# linear_buffered_sense.net
KiCad netlist of a schematic drawn in Altium Designer
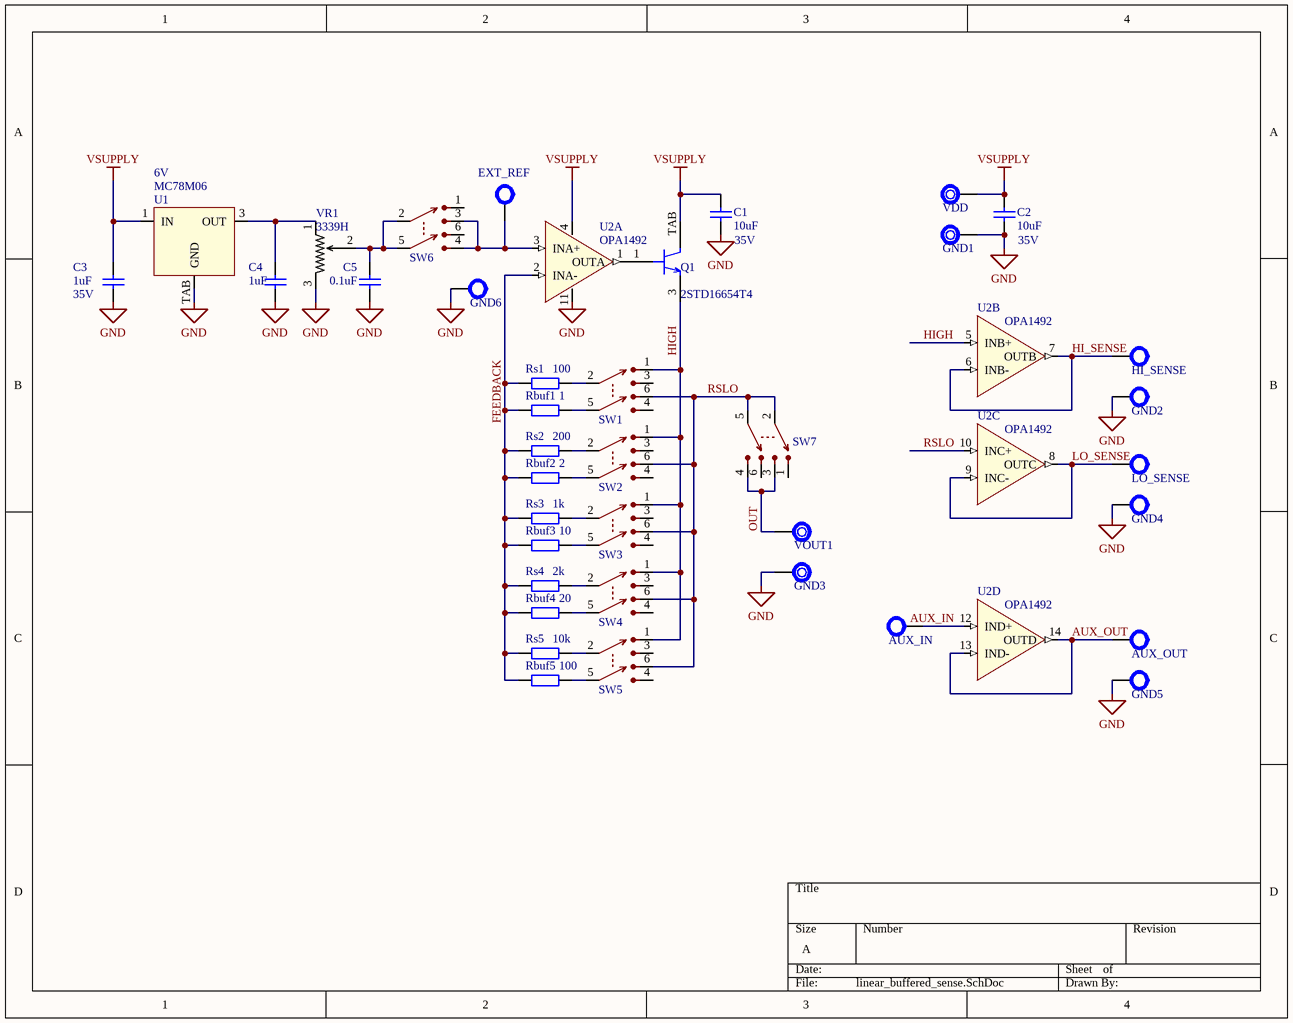
[diagram p0: linear_buffered_sense.SchDoc]

(export (version "E")
  (design (tool "Eeschema 10.0.6"))
  (components
    (comp (ref "AUX_IN")
      (value "Test Point")
      (footprint "Test Point - Large")
      (description "Test Point, large or small foot prints")
      (fields
        (field (name "MANUFACTURER PART NUMBER") "Example: 5000, 5013")
        (field (name "MANUFACTURER") "Keystone Electronics")
      )
      (libsource (lib "wisp") (part "Test Point"))
    )
    (comp (ref "AUX_OUT")
      (value "Test Point")
      (footprint "Test Point - Large")
      (description "Test Point, large or small foot prints")
      (fields
        (field (name "MANUFACTURER PART NUMBER") "Example: 5000, 5013")
        (field (name "MANUFACTURER") "Keystone Electronics")
      )
      (libsource (lib "wisp") (part "Test Point"))
    )
    (comp (ref "C1")
      (value "10uF")
      (footprint "1210-W")
      (description "Ceramic Capacitor (Surface Mount)")
      (fields
        (field (name "MANUFACTURER") "Generic Ceramic Chip Cap (TBD)")
        (field (name "RATING") "35V")
        (field (name "Comment") "Cap")
      )
      (libsource (lib "wisp") (part "Cap"))
    )
    (comp (ref "C2")
      (value "10uF")
      (footprint "1210-W")
      (description "Ceramic Capacitor (Surface Mount)")
      (fields
        (field (name "MANUFACTURER") "Generic Ceramic Chip Cap (TBD)")
        (field (name "RATING") "35V")
        (field (name "Comment") "Cap")
      )
      (libsource (lib "wisp") (part "Cap"))
    )
    (comp (ref "C3")
      (value "1uF")
      (footprint "0805")
      (description "Ceramic Capacitor (Surface Mount)")
      (fields
        (field (name "MANUFACTURER") "Generic Ceramic Chip Cap (TBD)")
        (field (name "RATING") "35V")
        (field (name "Comment") "Cap")
      )
      (libsource (lib "wisp") (part "Cap"))
    )
    (comp (ref "C4")
      (value "1uF")
      (footprint "0805")
      (description "Ceramic Capacitor (Surface Mount)")
      (fields (field (name "MANUFACTURER") "Generic Ceramic Chip Cap (TBD)") (field (name "Comment") "Cap"))
      (libsource (lib "wisp") (part "Cap"))
    )
    (comp (ref "C5")
      (value "0.1uF")
      (footprint "0805")
      (description "Ceramic Capacitor (Surface Mount)")
      (fields (field (name "MANUFACTURER") "Generic Ceramic Chip Cap (TBD)") (field (name "Comment") "Cap"))
      (libsource (lib "wisp") (part "Cap"))
    )
    (comp (ref "EXT_REF")
      (value "Test Point")
      (footprint "Test Point - Large")
      (description "Test Point, large or small foot prints")
      (fields
        (field (name "MANUFACTURER PART NUMBER") "Example: 5000, 5013")
        (field (name "MANUFACTURER") "Keystone Electronics")
      )
      (libsource (lib "wisp") (part "Test Point"))
    )
    (comp (ref "GND1")
      (value "BANANA")
      (footprint "BANANA")
      (description "Banana plug")
      (fields
        (field (name "MANUFACTURER PART NUMBER") "Example: 5000, 5013")
        (field (name "MANUFACTURER") "Keystone Electronics")
      )
      (libsource (lib "usmu") (part "BANANA"))
    )
    (comp (ref "GND2")
      (value "Test Point")
      (footprint "Test Point - Large")
      (description "Test Point, large or small foot prints")
      (fields
        (field (name "MANUFACTURER PART NUMBER") "Example: 5000, 5013")
        (field (name "MANUFACTURER") "Keystone Electronics")
      )
      (libsource (lib "wisp") (part "Test Point"))
    )
    (comp (ref "GND3")
      (value "BANANA")
      (footprint "BANANA")
      (description "Banana plug")
      (fields
        (field (name "MANUFACTURER PART NUMBER") "Example: 5000, 5013")
        (field (name "MANUFACTURER") "Keystone Electronics")
      )
      (libsource (lib "usmu") (part "BANANA"))
    )
    (comp (ref "GND4")
      (value "Test Point")
      (footprint "Test Point - Large")
      (description "Test Point, large or small foot prints")
      (fields
        (field (name "MANUFACTURER PART NUMBER") "Example: 5000, 5013")
        (field (name "MANUFACTURER") "Keystone Electronics")
      )
      (libsource (lib "wisp") (part "Test Point"))
    )
    (comp (ref "GND5")
      (value "Test Point")
      (footprint "Test Point - Large")
      (description "Test Point, large or small foot prints")
      (fields
        (field (name "MANUFACTURER PART NUMBER") "Example: 5000, 5013")
        (field (name "MANUFACTURER") "Keystone Electronics")
      )
      (libsource (lib "wisp") (part "Test Point"))
    )
    (comp (ref "GND6")
      (value "Test Point")
      (footprint "Test Point - Large")
      (description "Test Point, large or small foot prints")
      (fields
        (field (name "MANUFACTURER PART NUMBER") "Example: 5000, 5013")
        (field (name "MANUFACTURER") "Keystone Electronics")
      )
      (libsource (lib "wisp") (part "Test Point"))
    )
    (comp (ref "HI_SENSE")
      (value "Test Point")
      (footprint "Test Point - Large")
      (description "Test Point, large or small foot prints")
      (fields
        (field (name "MANUFACTURER PART NUMBER") "Example: 5000, 5013")
        (field (name "MANUFACTURER") "Keystone Electronics")
      )
      (libsource (lib "wisp") (part "Test Point"))
    )
    (comp (ref "LO_SENSE")
      (value "Test Point")
      (footprint "Test Point - Large")
      (description "Test Point, large or small foot prints")
      (fields
        (field (name "MANUFACTURER PART NUMBER") "Example: 5000, 5013")
        (field (name "MANUFACTURER") "Keystone Electronics")
      )
      (libsource (lib "wisp") (part "Test Point"))
    )
    (comp (ref "Q1")
      (value "2STD16654T4")
      (footprint "TO-252")
      (description "STMicroelectronics NPN BJT High Power")
      (fields
        (field (name "DIGI-KEY PART NUMBER") "568-6140-1-ND")
        (field (name "MANUFACTURER PART NUMBER") "BF1101WR,115")
      )
      (libsource (lib "usmu") (part "2STD16654T4"))
    )
    (comp (ref "Rbuf1")
      (value "1")
      (footprint "AXIAL-0.4")
      (description "Resistor")
      (fields (field (name "Comment") "Res2") (field (name "PUBLISHER") "Altium Limited"))
      (libsource (lib "altium-import") (part "root_2__Miscellaneous Devices.IntLib"))
    )
    (comp (ref "Rbuf2")
      (value "2")
      (footprint "AXIAL-0.4")
      (description "Resistor")
      (fields (field (name "Comment") "Res2") (field (name "PUBLISHER") "Altium Limited"))
      (libsource (lib "altium-import") (part "root_2__Miscellaneous Devices.IntLib"))
    )
    (comp (ref "Rbuf3")
      (value "10")
      (footprint "AXIAL-0.4")
      (description "Resistor")
      (fields (field (name "Comment") "Res2") (field (name "PUBLISHER") "Altium Limited"))
      (libsource (lib "altium-import") (part "root_2__Miscellaneous Devices.IntLib"))
    )
    (comp (ref "Rbuf4")
      (value "20")
      (footprint "AXIAL-0.4")
      (description "Resistor")
      (fields (field (name "Comment") "Res2") (field (name "PUBLISHER") "Altium Limited"))
      (libsource (lib "altium-import") (part "root_2__Miscellaneous Devices.IntLib"))
    )
    (comp (ref "Rbuf5")
      (value "100")
      (footprint "AXIAL-0.4")
      (description "Resistor")
      (fields (field (name "Comment") "Res2") (field (name "PUBLISHER") "Altium Limited"))
      (libsource (lib "altium-import") (part "root_2__Miscellaneous Devices.IntLib"))
    )
    (comp (ref "Rs1")
      (value "100")
      (footprint "AXIAL-0.4")
      (description "Resistor")
      (fields (field (name "Comment") "Res2") (field (name "PUBLISHER") "Altium Limited"))
      (libsource (lib "altium-import") (part "root_2__Miscellaneous Devices.IntLib"))
    )
    (comp (ref "Rs2")
      (value "200")
      (footprint "AXIAL-0.4")
      (description "Resistor")
      (fields (field (name "Comment") "Res2") (field (name "PUBLISHER") "Altium Limited"))
      (libsource (lib "altium-import") (part "root_2__Miscellaneous Devices.IntLib"))
    )
    (comp (ref "Rs3")
      (value "1k")
      (footprint "AXIAL-0.4")
      (description "Resistor")
      (fields (field (name "Comment") "Res2") (field (name "PUBLISHER") "Altium Limited"))
      (libsource (lib "altium-import") (part "root_2__Miscellaneous Devices.IntLib"))
    )
    (comp (ref "Rs4")
      (value "2k")
      (footprint "AXIAL-0.4")
      (description "Resistor")
      (fields (field (name "Comment") "Res2") (field (name "PUBLISHER") "Altium Limited"))
      (libsource (lib "altium-import") (part "root_2__Miscellaneous Devices.IntLib"))
    )
    (comp (ref "Rs5")
      (value "10k")
      (footprint "AXIAL-0.4")
      (description "Resistor")
      (fields (field (name "Comment") "Res2") (field (name "PUBLISHER") "Altium Limited"))
      (libsource (lib "altium-import") (part "root_2__Miscellaneous Devices.IntLib"))
    )
    (comp (ref "SW1")
      (value "JS202011CQN")
      (footprint "JS202011CQN_LABEL")
      (description "6-pin DPDT (tied) Slide Switch")
      (libsource (lib "usmu") (part "JS202011CQN_LABEL"))
    )
    (comp (ref "SW2")
      (value "JS202011CQN")
      (footprint "JS202011CQN_LABEL")
      (description "6-pin DPDT (tied) Slide Switch")
      (libsource (lib "usmu") (part "JS202011CQN_LABEL"))
    )
    (comp (ref "SW3")
      (value "JS202011CQN")
      (footprint "JS202011CQN_LABEL")
      (description "6-pin DPDT (tied) Slide Switch")
      (libsource (lib "usmu") (part "JS202011CQN_LABEL"))
    )
    (comp (ref "SW4")
      (value "JS202011CQN")
      (footprint "JS202011CQN_LABEL")
      (description "6-pin DPDT (tied) Slide Switch")
      (libsource (lib "usmu") (part "JS202011CQN_LABEL"))
    )
    (comp (ref "SW5")
      (value "JS202011CQN")
      (footprint "JS202011CQN_LABEL")
      (description "6-pin DPDT (tied) Slide Switch")
      (libsource (lib "usmu") (part "JS202011CQN_LABEL"))
    )
    (comp (ref "SW6")
      (value "JS202011CQN")
      (footprint "JS202011CQN")
      (description "6-pin DPDT (tied) Slide Switch")
      (libsource (lib "usmu") (part "JS202011CQN"))
    )
    (comp (ref "SW7")
      (value "JS202011CQN")
      (footprint "JS202011CQN")
      (description "6-pin DPDT (tied) Slide Switch")
      (libsource (lib "usmu") (part "JS202011CQN"))
    )
    (comp (ref "U1")
      (value "MC78M06")
      (footprint "TO-252")
      (description "500mA Positive Voltage Regulator")
      (fields (field (name "ALTIUM_VALUE") "6V"))
      (libsource (lib "usmu") (part "MC78M00"))
    )
    (comp (ref "U2")
      (value "OPA1492")
      (footprint "14-SOIC-TI")
      (description "OPAx192 Op-Amp Texas Instruments")
      (libsource (lib "usmu") (part "OPA1492"))
    )
    (comp (ref "VDD")
      (value "BANANA")
      (footprint "BANANA")
      (description "Banana plug")
      (fields
        (field (name "MANUFACTURER PART NUMBER") "Example: 5000, 5013")
        (field (name "MANUFACTURER") "Keystone Electronics")
      )
      (libsource (lib "usmu") (part "BANANA"))
    )
    (comp (ref "VOUT1")
      (value "BANANA")
      (footprint "BANANA")
      (description "Banana plug")
      (fields
        (field (name "MANUFACTURER PART NUMBER") "Example: 5000, 5013")
        (field (name "MANUFACTURER") "Keystone Electronics")
      )
      (libsource (lib "usmu") (part "BANANA"))
    )
    (comp (ref "VR1")
      (value "3339H")
      (footprint "3339H")
      (description "Bourns 4-turn Trimpot")
      (libsource (lib "usmu") (part "3339H"))
    )
  )
  (nets
    (net (code "2") (name "/AUX_OUT") (class "Default")
      (node (ref "AUX_OUT") (pin "0") (pinfunction "0_0") (pintype "passive"))
      (node (ref "U2") (pin "13") (pinfunction "IND-_13") (pintype "input"))
      (node (ref "U2") (pin "14") (pinfunction "OUTD_14") (pintype "output"))
    )
    (net (code "3") (name "/FEEDBACK") (class "Default")
      (node (ref "Rbuf1") (pin "2") (pinfunction "2_2") (pintype "passive"))
      (node (ref "Rbuf2") (pin "2") (pinfunction "2_2") (pintype "passive"))
      (node (ref "Rbuf3") (pin "2") (pinfunction "2_2") (pintype "passive"))
      (node (ref "Rbuf4") (pin "2") (pinfunction "2_2") (pintype "passive"))
      (node (ref "Rbuf5") (pin "2") (pinfunction "2_2") (pintype "passive"))
      (node (ref "Rs1") (pin "2") (pinfunction "2_2") (pintype "passive"))
      (node (ref "Rs2") (pin "2") (pinfunction "2_2") (pintype "passive"))
      (node (ref "Rs3") (pin "2") (pinfunction "2_2") (pintype "passive"))
      (node (ref "Rs4") (pin "2") (pinfunction "2_2") (pintype "passive"))
      (node (ref "Rs5") (pin "2") (pinfunction "2_2") (pintype "passive"))
      (node (ref "U2") (pin "2") (pinfunction "INA-_2") (pintype "input"))
    )
    (net (code "4") (name "/HIGH") (class "Default")
      (node (ref "Q1") (pin "3") (pinfunction "E_3") (pintype "passive"))
      (node (ref "SW1") (pin "1") (pintype "passive"))
      (node (ref "SW2") (pin "1") (pintype "passive"))
      (node (ref "SW3") (pin "1") (pintype "passive"))
      (node (ref "SW4") (pin "1") (pintype "passive"))
      (node (ref "SW5") (pin "1") (pintype "passive"))
      (node (ref "U2") (pin "5") (pinfunction "INB+_5") (pintype "input"))
    )
    (net (code "5") (name "/HI_SENSE") (class "Default")
      (node (ref "HI_SENSE") (pin "0") (pinfunction "0_0") (pintype "passive"))
      (node (ref "U2") (pin "6") (pinfunction "INB-_6") (pintype "input"))
      (node (ref "U2") (pin "7") (pinfunction "OUTB_7") (pintype "output"))
    )
    (net (code "6") (name "/LO_SENSE") (class "Default")
      (node (ref "LO_SENSE") (pin "0") (pinfunction "0_0") (pintype "passive"))
      (node (ref "U2") (pin "8") (pinfunction "OUTC_8") (pintype "output"))
      (node (ref "U2") (pin "9") (pinfunction "INC-_9") (pintype "input"))
    )
    (net (code "7") (name "/OUT") (class "Default")
      (node (ref "SW7") (pin "3") (pintype "passive"))
      (node (ref "SW7") (pin "4") (pintype "passive"))
      (node (ref "VOUT1") (pin "0") (pinfunction "0_0") (pintype "passive"))
    )
    (net (code "8") (name "/RSLO") (class "Default")
      (node (ref "SW1") (pin "6") (pintype "passive"))
      (node (ref "SW2") (pin "6") (pintype "passive"))
      (node (ref "SW3") (pin "6") (pintype "passive"))
      (node (ref "SW4") (pin "6") (pintype "passive"))
      (node (ref "SW5") (pin "6") (pintype "passive"))
      (node (ref "SW7") (pin "2") (pintype "passive"))
      (node (ref "SW7") (pin "5") (pinfunction "0_5") (pintype "passive"))
      (node (ref "U2") (pin "10") (pinfunction "INC+_10") (pintype "input"))
    )
    (net (code "9") (name "GND") (class "Default")
      (node (ref "C1") (pin "1") (pinfunction "1_1") (pintype "passive"))
      (node (ref "C2") (pin "1") (pinfunction "1_1") (pintype "passive"))
      (node (ref "C3") (pin "1") (pinfunction "1_1") (pintype "passive"))
      (node (ref "C4") (pin "1") (pinfunction "1_1") (pintype "passive"))
      (node (ref "C5") (pin "1") (pinfunction "1_1") (pintype "passive"))
      (node (ref "GND1") (pin "0") (pinfunction "0_0") (pintype "passive"))
      (node (ref "GND2") (pin "0") (pinfunction "0_0") (pintype "passive"))
      (node (ref "GND3") (pin "0") (pinfunction "0_0") (pintype "passive"))
      (node (ref "GND4") (pin "0") (pinfunction "0_0") (pintype "passive"))
      (node (ref "GND5") (pin "0") (pinfunction "0_0") (pintype "passive"))
      (node (ref "GND6") (pin "0") (pinfunction "0_0") (pintype "passive"))
      (node (ref "U1") (pin "TAB") (pinfunction "GND_TAB") (pintype "passive"))
      (node (ref "U2") (pin "11") (pinfunction "V-_11") (pintype "power_in"))
      (node (ref "VR1") (pin "3") (pinfunction "CW_3") (pintype "passive"))
    )
    (net (code "10") (name "Net-(Q1-B)") (class "Default")
      (node (ref "Q1") (pin "1") (pinfunction "B_1") (pintype "passive"))
      (node (ref "U2") (pin "1") (pinfunction "OUTA_1") (pintype "output"))
    )
    (net (code "11") (name "Net-(Rs1-Pad1)") (class "Default")
      (node (ref "Rs1") (pin "1") (pinfunction "1_1") (pintype "passive"))
      (node (ref "SW1") (pin "2") (pintype "passive"))
    )
    (net (code "12") (name "Net-(Rs2-Pad1)") (class "Default")
      (node (ref "Rs2") (pin "1") (pinfunction "1_1") (pintype "passive"))
      (node (ref "SW2") (pin "2") (pintype "passive"))
    )
    (net (code "13") (name "Net-(Rs3-Pad1)") (class "Default")
      (node (ref "Rs3") (pin "1") (pinfunction "1_1") (pintype "passive"))
      (node (ref "SW3") (pin "2") (pintype "passive"))
    )
    (net (code "14") (name "Net-(Rs4-Pad1)") (class "Default")
      (node (ref "Rs4") (pin "1") (pinfunction "1_1") (pintype "passive"))
      (node (ref "SW4") (pin "2") (pintype "passive"))
    )
    (net (code "15") (name "Net-(Rs5-Pad1)") (class "Default")
      (node (ref "Rs5") (pin "1") (pinfunction "1_1") (pintype "passive"))
      (node (ref "SW5") (pin "2") (pintype "passive"))
    )
    (net (code "16") (name "Net-(SW1-0)") (class "Default")
      (node (ref "Rbuf1") (pin "1") (pinfunction "1_1") (pintype "passive"))
      (node (ref "SW1") (pin "5") (pinfunction "0_5") (pintype "passive"))
    )
    (net (code "17") (name "Net-(SW2-0)") (class "Default")
      (node (ref "Rbuf2") (pin "1") (pinfunction "1_1") (pintype "passive"))
      (node (ref "SW2") (pin "5") (pinfunction "0_5") (pintype "passive"))
    )
    (net (code "18") (name "Net-(SW3-0)") (class "Default")
      (node (ref "Rbuf3") (pin "1") (pinfunction "1_1") (pintype "passive"))
      (node (ref "SW3") (pin "5") (pinfunction "0_5") (pintype "passive"))
    )
    (net (code "19") (name "Net-(SW4-0)") (class "Default")
      (node (ref "Rbuf4") (pin "1") (pinfunction "1_1") (pintype "passive"))
      (node (ref "SW4") (pin "5") (pinfunction "0_5") (pintype "passive"))
    )
    (net (code "20") (name "Net-(SW5-0)") (class "Default")
      (node (ref "Rbuf5") (pin "1") (pinfunction "1_1") (pintype "passive"))
      (node (ref "SW5") (pin "5") (pinfunction "0_5") (pintype "passive"))
    )
    (net (code "21") (name "Net-(SW6-0)") (class "Default")
      (node (ref "C5") (pin "2") (pinfunction "2_2") (pintype "passive"))
      (node (ref "SW6") (pin "2") (pintype "passive"))
      (node (ref "SW6") (pin "5") (pinfunction "0_5") (pintype "passive"))
      (node (ref "VR1") (pin "2") (pinfunction "WIPER_2") (pintype "passive"))
    )
    (net (code "22") (name "Net-(U1-OUT)") (class "Default")
      (node (ref "C4") (pin "2") (pinfunction "2_2") (pintype "passive"))
      (node (ref "U1") (pin "3") (pinfunction "OUT_3") (pintype "passive"))
      (node (ref "VR1") (pin "1") (pinfunction "CCW_1") (pintype "passive"))
    )
    (net (code "23") (name "Net-(U2A-INA+)") (class "Default")
      (node (ref "EXT_REF") (pin "0") (pinfunction "0_0") (pintype "passive"))
      (node (ref "SW6") (pin "3") (pintype "passive"))
      (node (ref "SW6") (pin "4") (pintype "passive"))
      (node (ref "U2") (pin "3") (pinfunction "INA+_3") (pintype "input"))
    )
    (net (code "24") (name "Net-(U2D-IND+)") (class "Default")
      (node (ref "AUX_IN") (pin "0") (pinfunction "0_0") (pintype "passive"))
      (node (ref "U2") (pin "12") (pinfunction "IND+_12") (pintype "input"))
    )
    (net (code "25") (name "VSUPPLY") (class "Default")
      (node (ref "C1") (pin "2") (pinfunction "2_2") (pintype "passive"))
      (node (ref "C2") (pin "2") (pinfunction "2_2") (pintype "passive"))
      (node (ref "C3") (pin "2") (pinfunction "2_2") (pintype "passive"))
      (node (ref "Q1") (pin "TAB") (pinfunction "C_TAB") (pintype "passive"))
      (node (ref "U1") (pin "1") (pinfunction "IN_1") (pintype "passive"))
      (node (ref "U2") (pin "4") (pinfunction "V+_4") (pintype "power_in"))
      (node (ref "VDD") (pin "0") (pinfunction "0_0") (pintype "passive"))
    )
    (net (code "26") (name "unconnected-(SW1-Pad3)") (class "Default")
      (node (ref "SW1") (pin "3") (pintype "passive"))
    )
    (net (code "27") (name "unconnected-(SW1-Pad4)") (class "Default")
      (node (ref "SW1") (pin "4") (pintype "passive"))
    )
    (net (code "28") (name "unconnected-(SW2-Pad3)") (class "Default")
      (node (ref "SW2") (pin "3") (pintype "passive"))
    )
    (net (code "29") (name "unconnected-(SW2-Pad4)") (class "Default")
      (node (ref "SW2") (pin "4") (pintype "passive"))
    )
    (net (code "30") (name "unconnected-(SW3-Pad3)") (class "Default")
      (node (ref "SW3") (pin "3") (pintype "passive"))
    )
    (net (code "31") (name "unconnected-(SW3-Pad4)") (class "Default")
      (node (ref "SW3") (pin "4") (pintype "passive"))
    )
    (net (code "32") (name "unconnected-(SW4-Pad3)") (class "Default")
      (node (ref "SW4") (pin "3") (pintype "passive"))
    )
    (net (code "33") (name "unconnected-(SW4-Pad4)") (class "Default")
      (node (ref "SW4") (pin "4") (pintype "passive"))
    )
    (net (code "34") (name "unconnected-(SW5-Pad3)") (class "Default")
      (node (ref "SW5") (pin "3") (pintype "passive"))
    )
    (net (code "35") (name "unconnected-(SW5-Pad4)") (class "Default")
      (node (ref "SW5") (pin "4") (pintype "passive"))
    )
    (net (code "36") (name "unconnected-(SW6-Pad1)") (class "Default")
      (node (ref "SW6") (pin "1") (pintype "passive"))
    )
    (net (code "37") (name "unconnected-(SW6-Pad6)") (class "Default")
      (node (ref "SW6") (pin "6") (pintype "passive"))
    )
    (net (code "38") (name "unconnected-(SW7-Pad1)") (class "Default")
      (node (ref "SW7") (pin "1") (pintype "passive"))
    )
    (net (code "39") (name "unconnected-(SW7-Pad6)") (class "Default")
      (node (ref "SW7") (pin "6") (pintype "passive"))
    )
  )
)
